# capstone.net
KiCad netlist of a schematic drawn in EAGLE
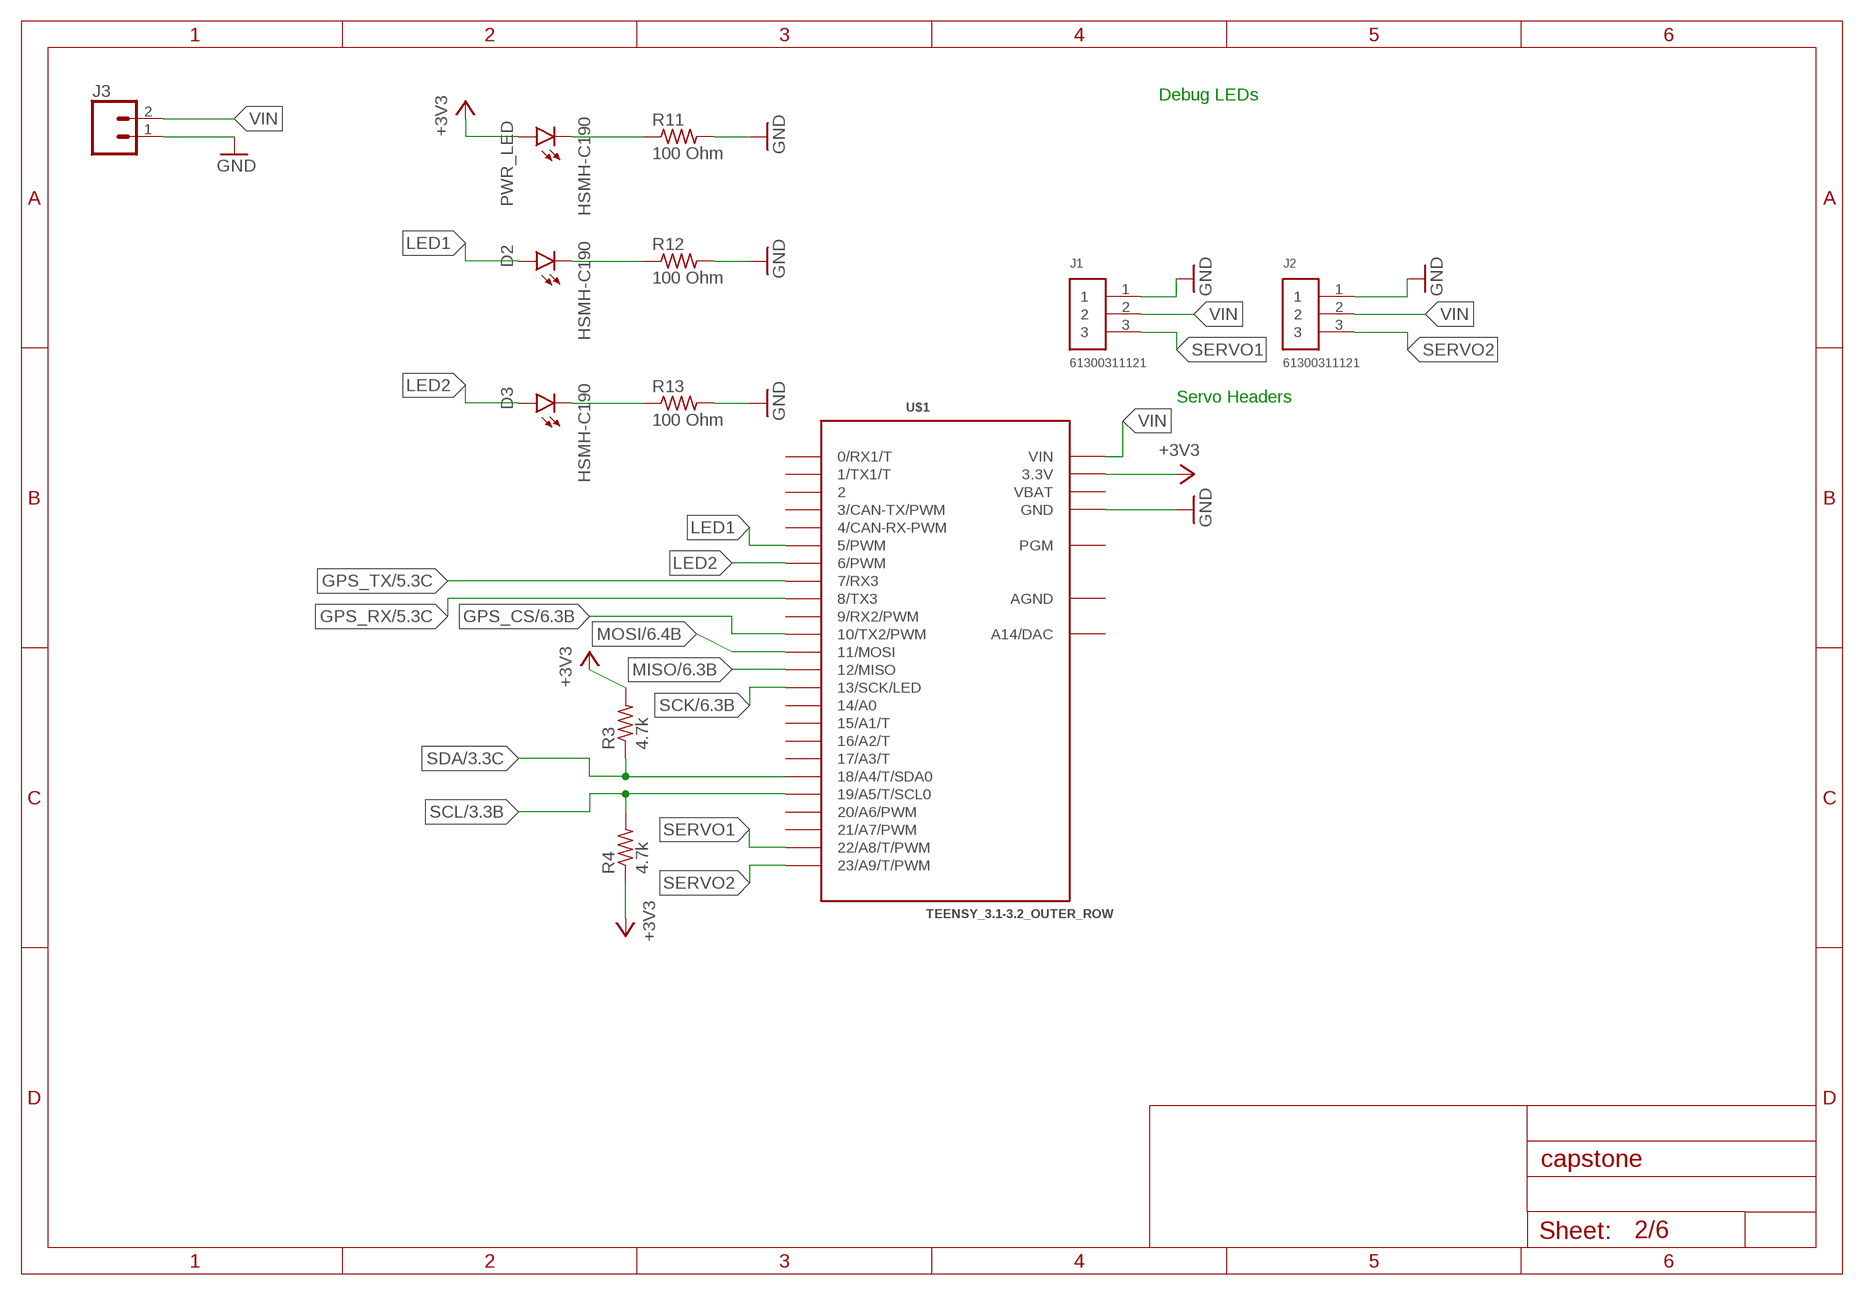
[diagram p0: schematic, sheet 2]
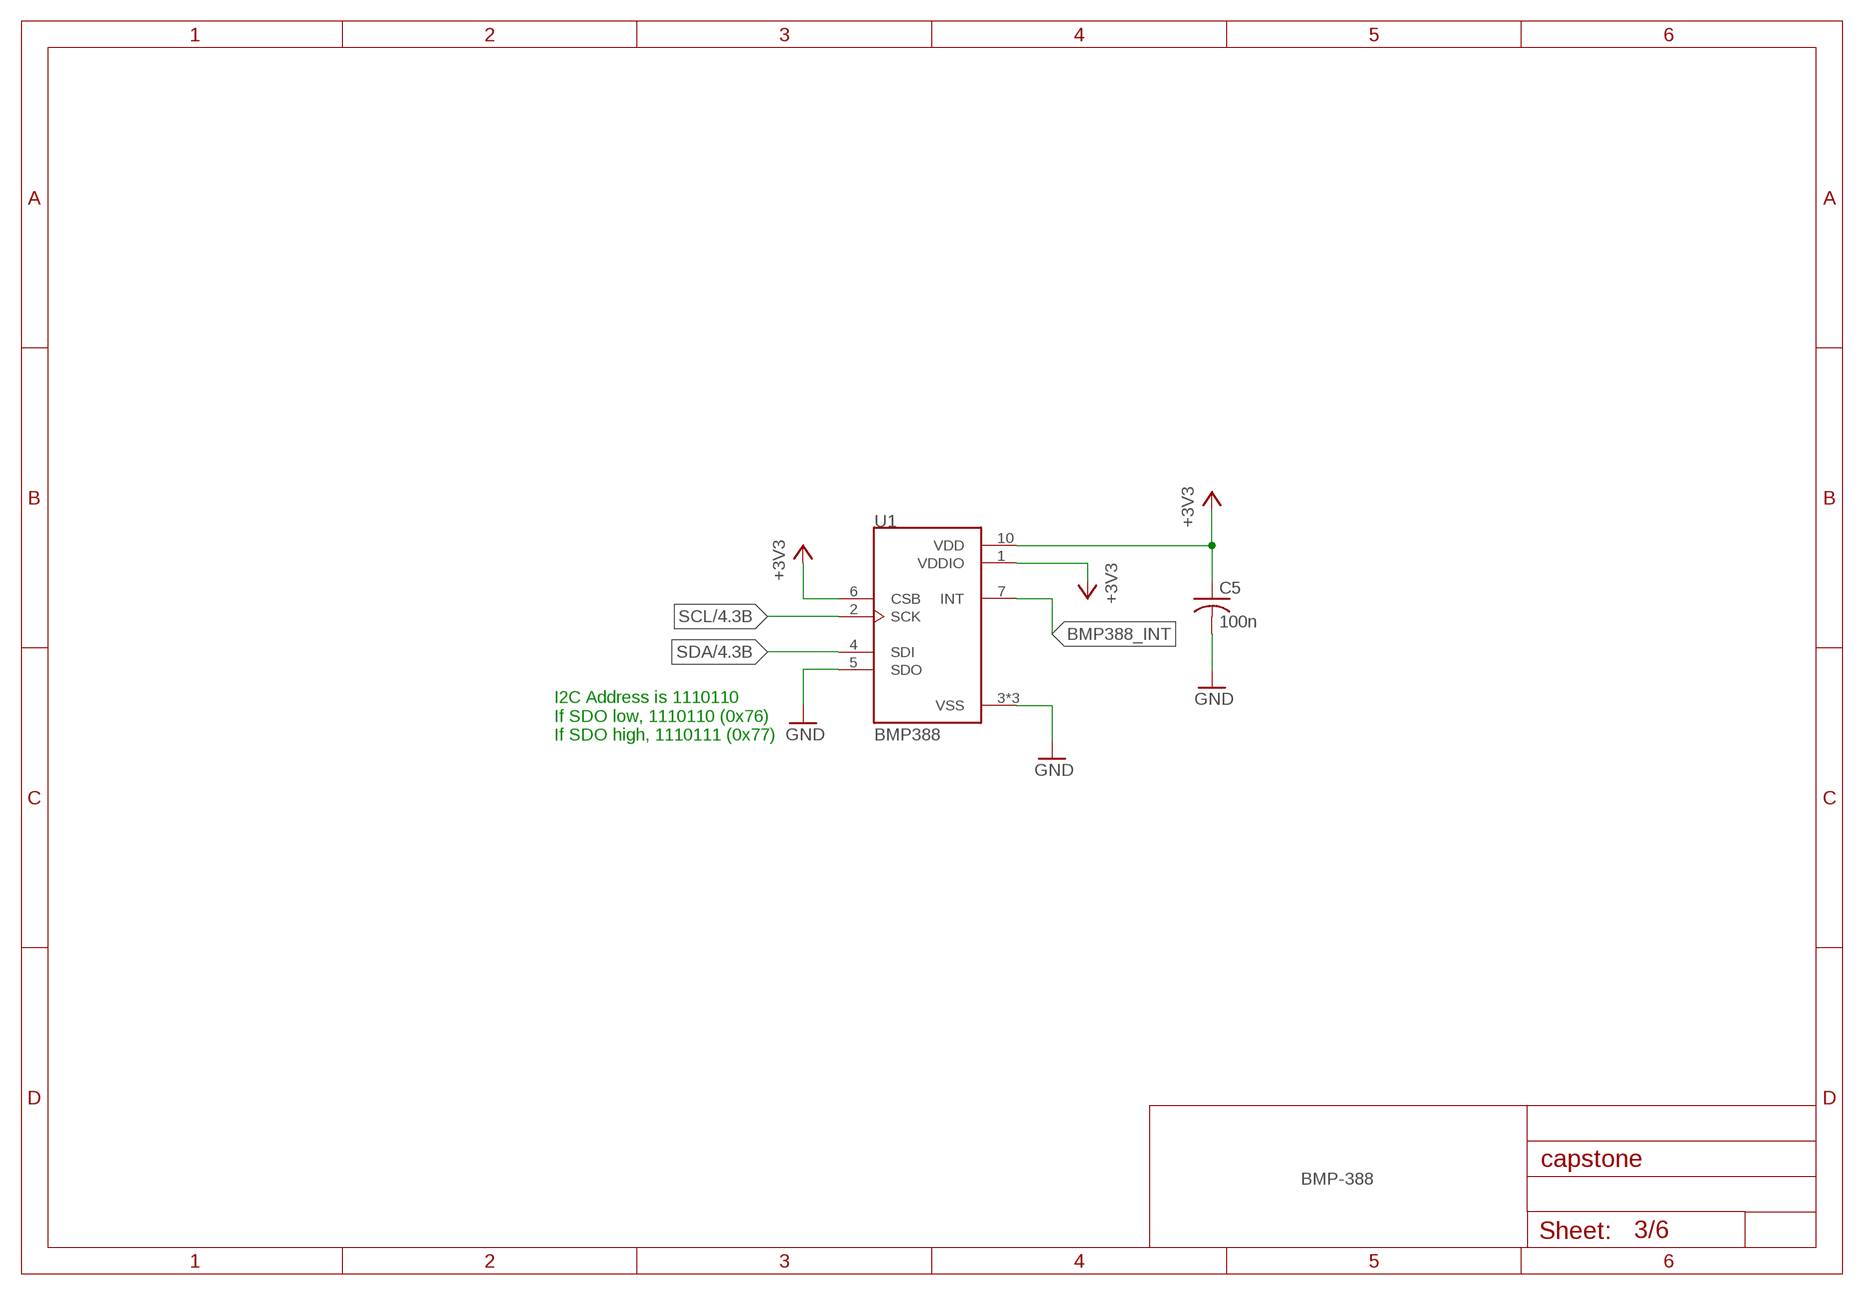
[diagram p1: schematic, sheet 3]
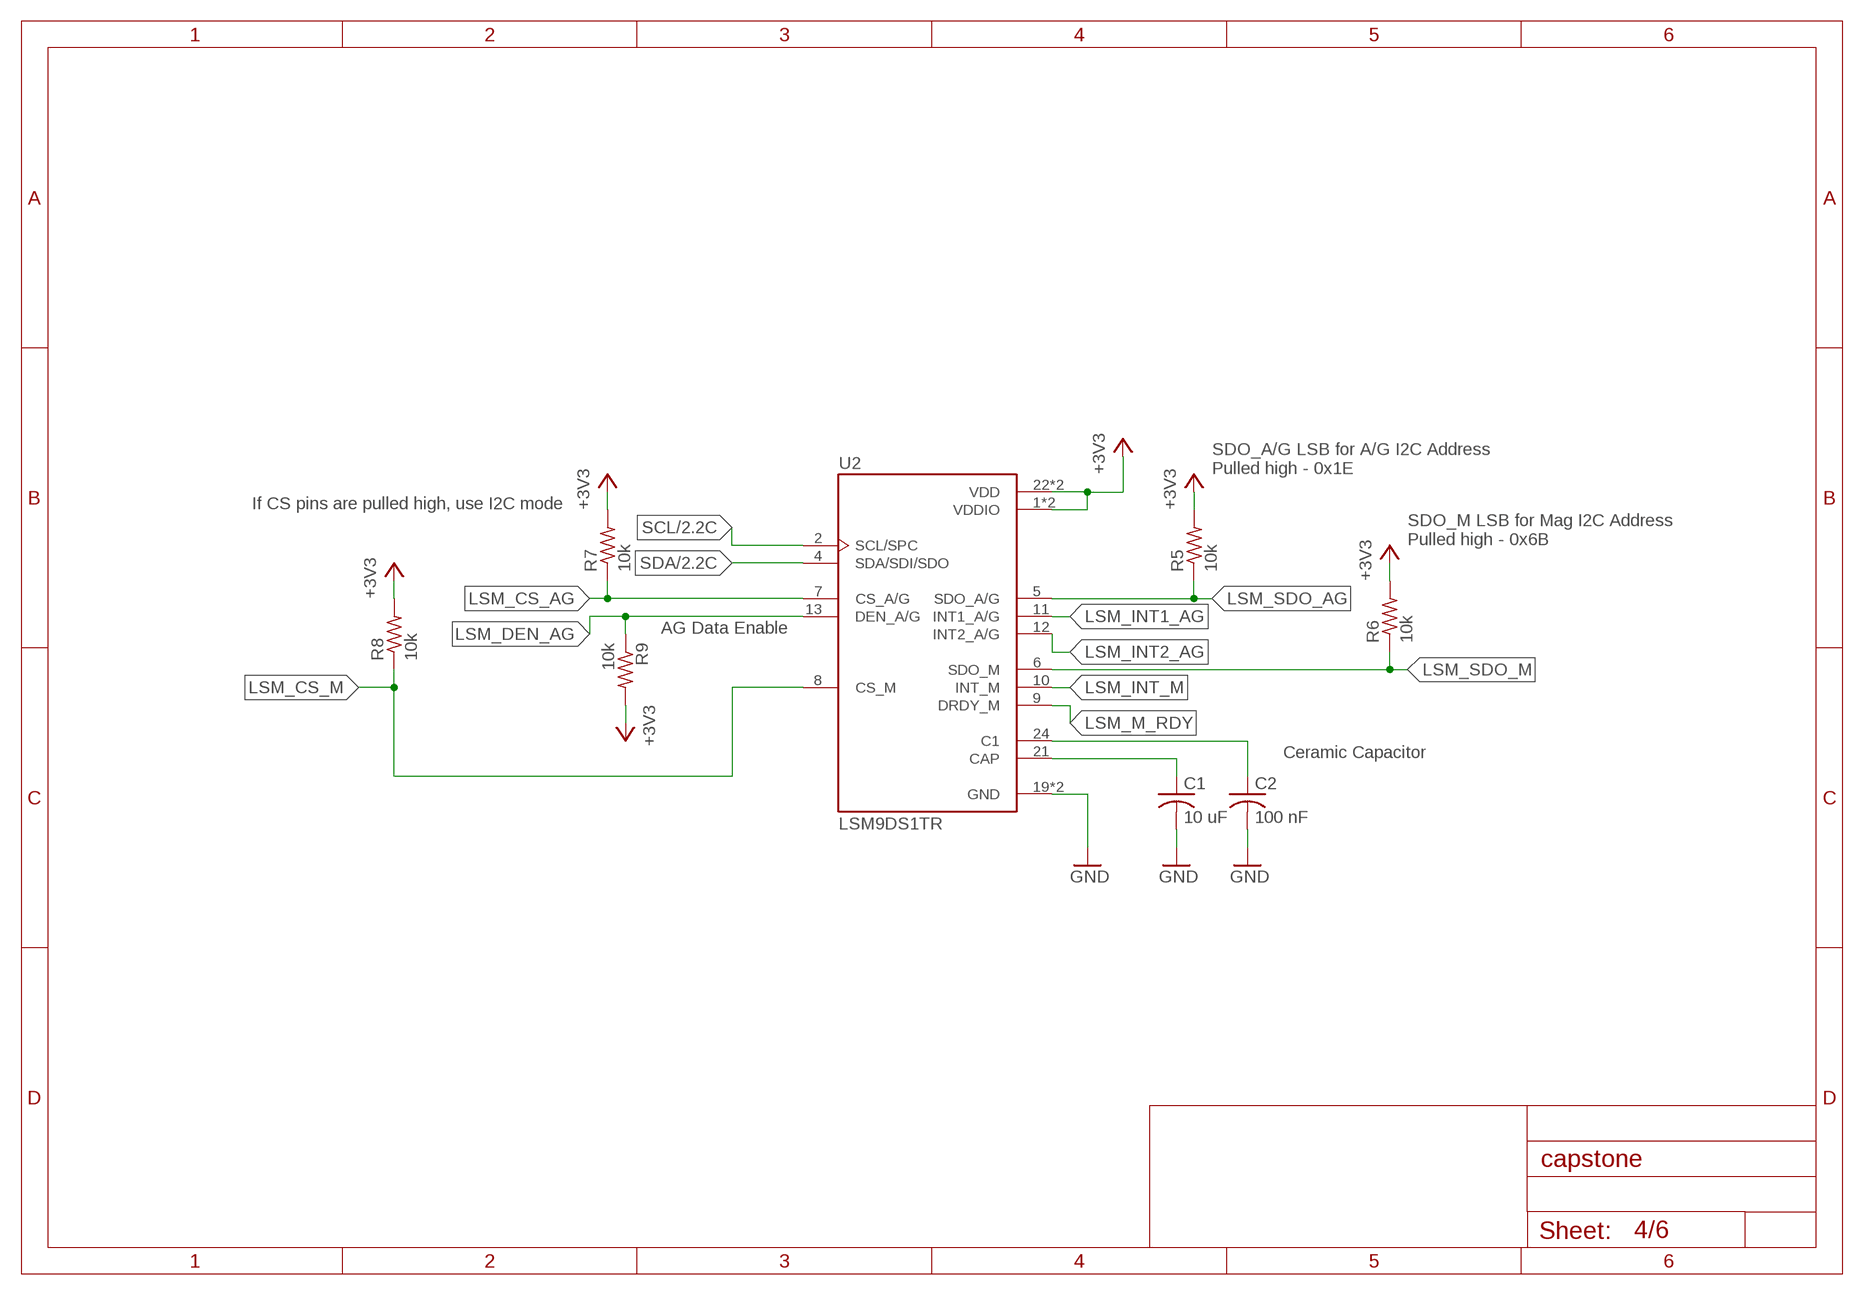
[diagram p2: schematic, sheet 4]
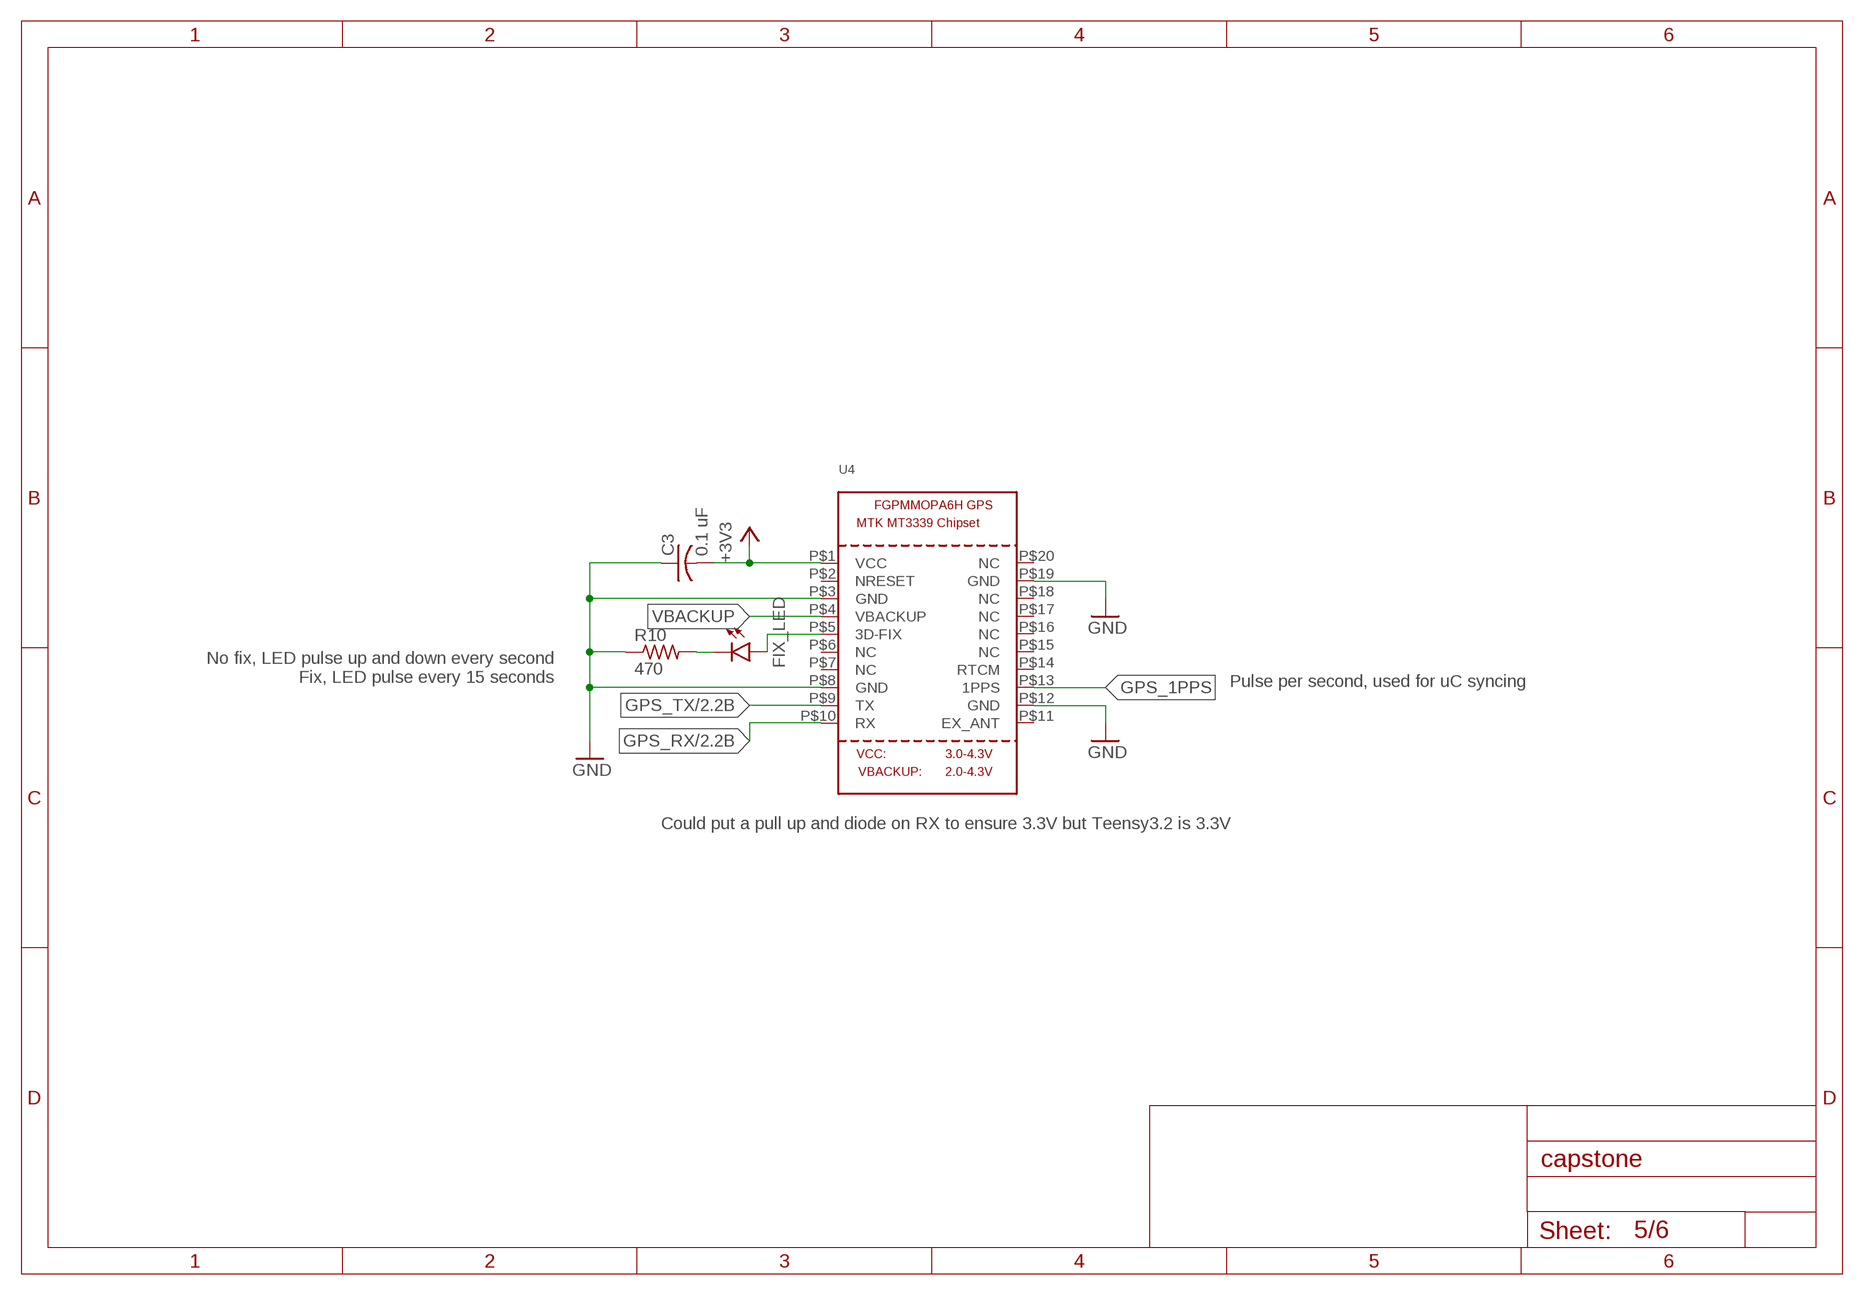
[diagram p3: schematic, sheet 5]
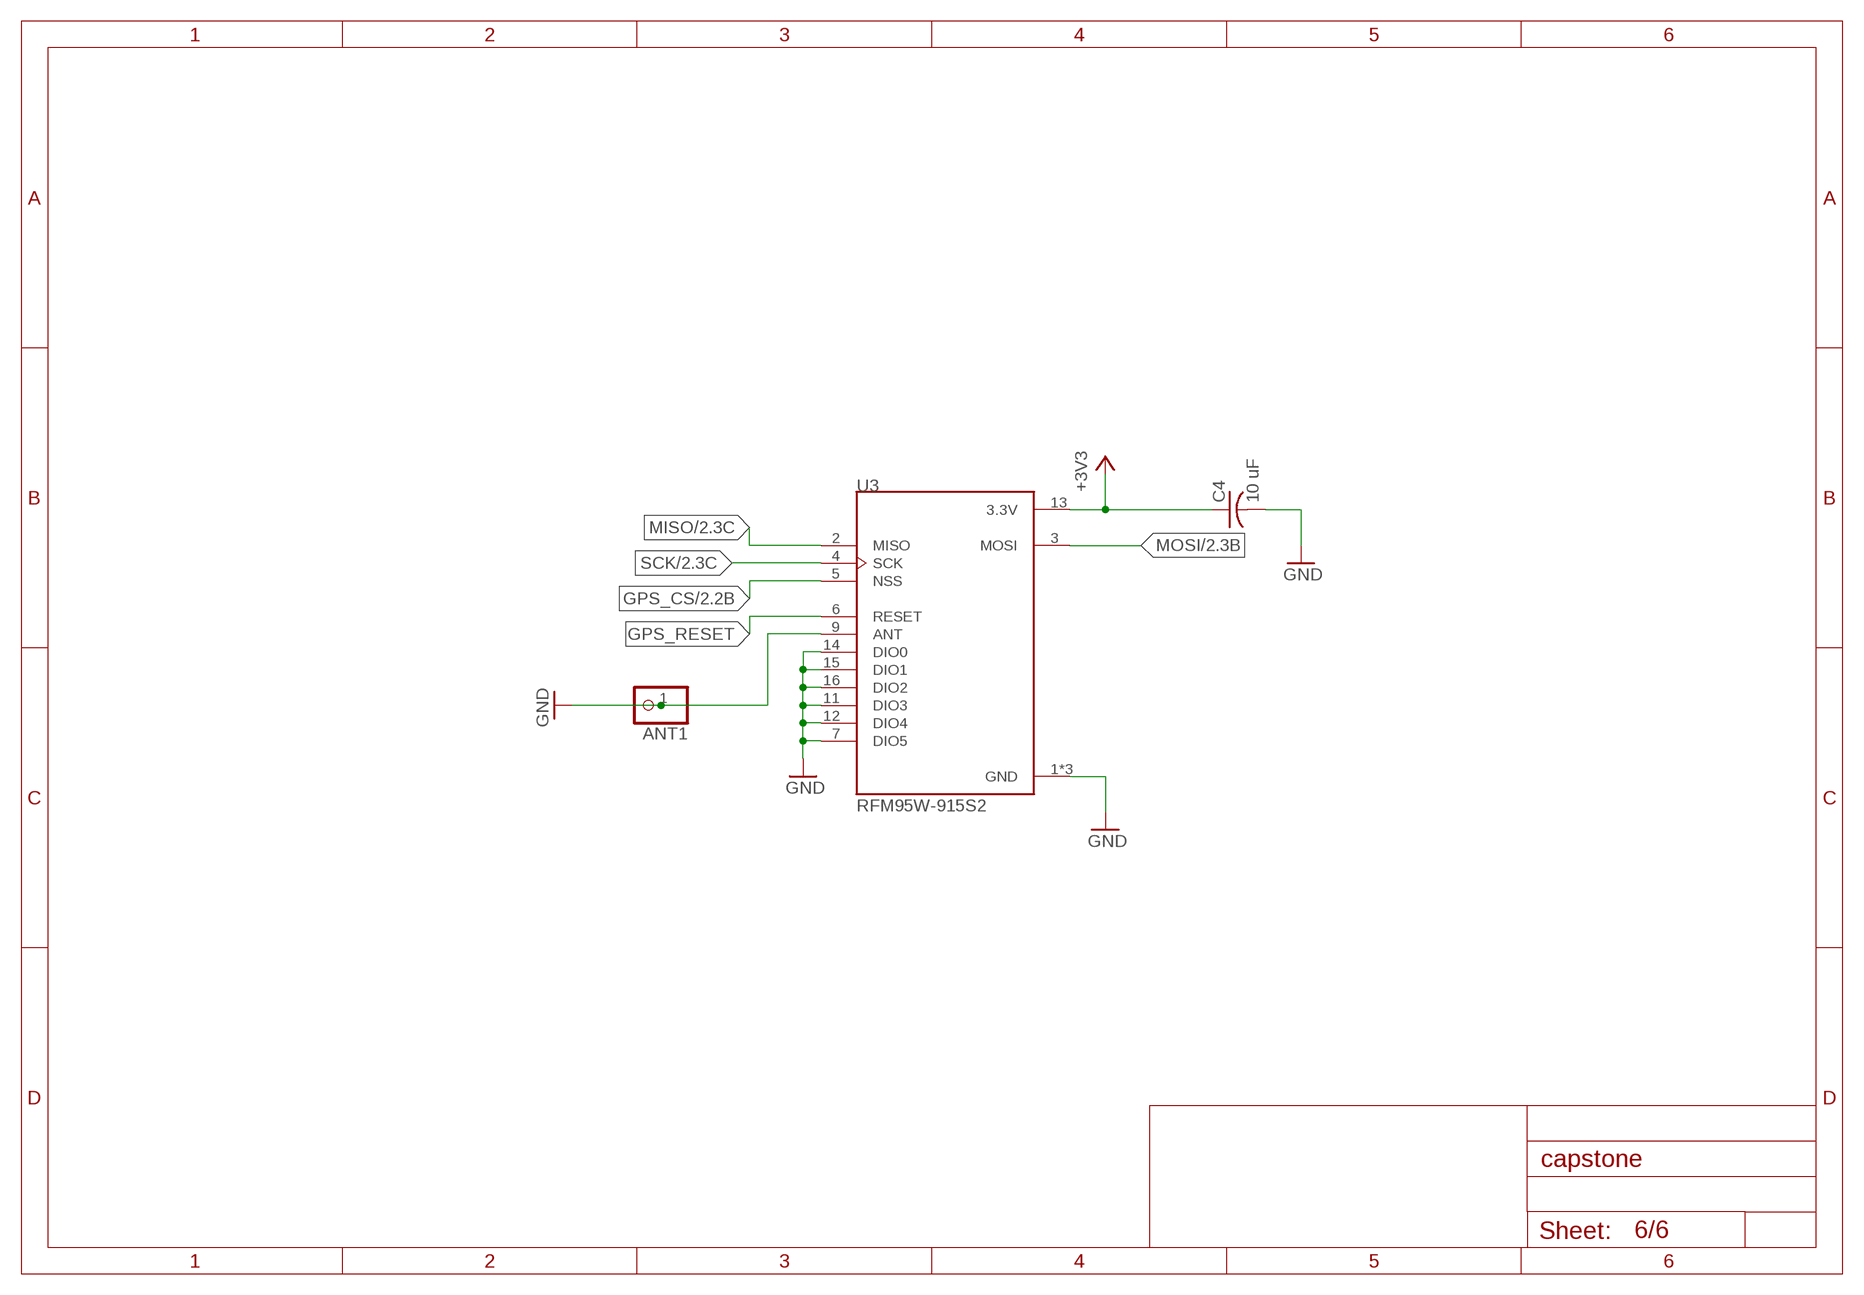
[diagram p4: schematic, sheet 6]

(export (version "E")
  (design (tool "Eeschema 10.0.6"))
  (components
    (comp (ref "D2")
      (value "HSMH-C190")
      (footprint "eagle-import:LED-0603")
      (fields
        (field (name "DIGIKEY_PART_NUMBER") "516-1420-1-ND")
        (field (name "MANUFACTURER") "Broadcom Limited")
        (field (name "CREATED_BY") "PCBLayout.com")
      )
      (libsource (lib "eagle-import") (part "HSMH-C190"))
    )
    (comp (ref "D3")
      (value "HSMH-C190")
      (footprint "eagle-import:LED-0603")
      (fields
        (field (name "DIGIKEY_PART_NUMBER") "516-1420-1-ND")
        (field (name "MANUFACTURER") "Broadcom Limited")
        (field (name "CREATED_BY") "PCBLayout.com")
      )
      (libsource (lib "eagle-import") (part "HSMH-C190"))
    )
    (comp (ref "J1")
      (value "61300311121")
      (footprint "eagle-import:61300311121")
      (fields
        (field (name "DIGI_KEY_PART_NUMBER") "732-5316-ND")
        (field (name "MANUFACTURER") "Wurth Electronics Inc.")
        (field (name "CREATED_BY") "PCBLayout.com")
      )
      (libsource (lib "eagle-import") (part "61300311121"))
    )
    (comp (ref "J2")
      (value "61300311121")
      (footprint "eagle-import:61300311121")
      (fields
        (field (name "DIGI_KEY_PART_NUMBER") "732-5316-ND")
        (field (name "MANUFACTURER") "Wurth Electronics Inc.")
        (field (name "CREATED_BY") "PCBLayout.com")
      )
      (libsource (lib "eagle-import") (part "61300311121"))
    )
    (comp (ref "J3")
      (value "CONN_02")
      (footprint "eagle-import:1X02")
      (libsource (lib "eagle-import") (part "CONN_02"))
    )
    (comp (ref "PWR_LED")
      (value "HSMH-C190")
      (footprint "eagle-import:LED-0603")
      (fields
        (field (name "DIGIKEY_PART_NUMBER") "516-1420-1-ND")
        (field (name "MANUFACTURER") "Broadcom Limited")
        (field (name "CREATED_BY") "PCBLayout.com")
      )
      (libsource (lib "eagle-import") (part "HSMH-C190"))
    )
    (comp (ref "R3")
      (value "4.7k")
      (footprint "eagle-import:R0603")
      (libsource (lib "eagle-import") (part "R-US_R0603"))
    )
    (comp (ref "R4")
      (value "4.7k")
      (footprint "eagle-import:R0603")
      (libsource (lib "eagle-import") (part "R-US_R0603"))
    )
    (comp (ref "R11")
      (value "100 Ohm")
      (footprint "eagle-import:R0603")
      (libsource (lib "eagle-import") (part "R-US_R0603"))
    )
    (comp (ref "R12")
      (value "100 Ohm")
      (footprint "eagle-import:R0603")
      (libsource (lib "eagle-import") (part "R-US_R0603"))
    )
    (comp (ref "R13")
      (value "100 Ohm")
      (footprint "eagle-import:R0603")
      (libsource (lib "eagle-import") (part "R-US_R0603"))
    )
    (comp (ref "U$1")
      (value "TEENSY_3.1-3.2_OUTER_ROW")
      (footprint "eagle-import:TEENSY_3.0-3.2&LC_OUTER_ROW")
      (libsource (lib "eagle-import") (part "TEENSY_3.1-3.2_OUTER_ROW"))
    )
    (comp (ref "C3")
      (value "0.1 uF")
      (footprint "eagle-import:C0603")
      (libsource (lib "eagle-import") (part "resistor_348_C-USC0603"))
    )
    (comp (ref "FIX_LED")
      (value "HSMH-C190")
      (footprint "eagle-import:LED-0603")
      (fields
        (field (name "DIGIKEY_PART_NUMBER") "516-1420-1-ND")
        (field (name "MANUFACTURER") "Broadcom Limited")
        (field (name "CREATED_BY") "PCBLayout.com")
      )
      (libsource (lib "eagle-import") (part "HSMH-C190"))
    )
    (comp (ref "R10")
      (value "470")
      (footprint "eagle-import:R0603")
      (libsource (lib "eagle-import") (part "R-US_R0603"))
    )
    (comp (ref "U4")
      (value "GPS_FGPMMOPA6H")
      (footprint "eagle-import:FGPMMOPA6H")
      (libsource (lib "eagle-import") (part "GPS_FGPMMOPA6H"))
    )
    (comp (ref "C1")
      (value "10 uF")
      (footprint "eagle-import:C0603")
      (libsource (lib "eagle-import") (part "resistor_348_C-USC0603"))
    )
    (comp (ref "C2")
      (value "100 nF")
      (footprint "eagle-import:C0603")
      (libsource (lib "eagle-import") (part "resistor_348_C-USC0603"))
    )
    (comp (ref "R5")
      (value "10k")
      (footprint "eagle-import:R0603")
      (libsource (lib "eagle-import") (part "R-US_R0603"))
    )
    (comp (ref "R6")
      (value "10k")
      (footprint "eagle-import:R0603")
      (libsource (lib "eagle-import") (part "R-US_R0603"))
    )
    (comp (ref "R7")
      (value "10k")
      (footprint "eagle-import:R0603")
      (libsource (lib "eagle-import") (part "R-US_R0603"))
    )
    (comp (ref "R8")
      (value "10k")
      (footprint "eagle-import:R0603")
      (libsource (lib "eagle-import") (part "R-US_R0603"))
    )
    (comp (ref "R9")
      (value "10k")
      (footprint "eagle-import:R0603")
      (libsource (lib "eagle-import") (part "R-US_R0603"))
    )
    (comp (ref "U2")
      (value "LSM9DS1TR")
      (footprint "eagle-import:PQFN43P300X350X102-24N")
      (fields (field (name "DIGI-KEY_PART_NUMBER") "497-14946-1-ND") (field (name "MF") "STMicroelectronics"))
      (libsource (lib "eagle-import") (part "LSM9DS1TR"))
    )
    (comp (ref "C5")
      (value "100n")
      (footprint "eagle-import:C0603")
      (libsource (lib "eagle-import") (part "C-USC0603"))
    )
    (comp (ref "U1")
      (value "BMP388")
      (footprint "eagle-import:PQFN50P200X200X80-10N")
      (fields (field (name "DIGI-KEY_PART_NUMBER") "828-1079-1-ND") (field (name "MF") "Bosch Sensortec"))
      (libsource (lib "eagle-import") (part "BMP388"))
    )
    (comp (ref "ANT1")
      (value "PINHD-1X1")
      (footprint "eagle-import:1X01")
      (libsource (lib "eagle-import") (part "PINHD-1X1"))
    )
    (comp (ref "C4")
      (value "10 uF")
      (footprint "eagle-import:C0603")
      (libsource (lib "eagle-import") (part "resistor_348_C-USC0603"))
    )
    (comp (ref "U3")
      (value "RFM95W-915S2")
      (footprint "eagle-import:XCVR_RFM95W-915S2")
      (fields (field (name "DIGI-KEY_PART_NUMBER") "RFM95W-915S2-ND") (field (name "MF") "RF Solutions"))
      (libsource (lib "eagle-import") (part "RFM95W-915S2"))
    )
  )
  (nets
    (net (code "1") (name "+3V3") (class "Default")
      (node (ref "C3") (pin "2") (pinfunction "2_2") (pintype "passive"))
      (node (ref "C4") (pin "1") (pinfunction "1_1") (pintype "passive"))
      (node (ref "C5") (pin "1") (pinfunction "1_1") (pintype "passive"))
      (node (ref "PWR_LED") (pin "A") (pinfunction "A_A") (pintype "passive"))
      (node (ref "R3") (pin "2") (pinfunction "2_2") (pintype "passive"))
      (node (ref "R4") (pin "1") (pinfunction "1_1") (pintype "passive"))
      (node (ref "R5") (pin "2") (pinfunction "2_2") (pintype "passive"))
      (node (ref "R6") (pin "2") (pinfunction "2_2") (pintype "passive"))
      (node (ref "R7") (pin "2") (pinfunction "2_2") (pintype "passive"))
      (node (ref "R8") (pin "2") (pinfunction "2_2") (pintype "passive"))
      (node (ref "R9") (pin "2") (pinfunction "2_2") (pintype "passive"))
      (node (ref "U$1") (pin "3.3V") (pinfunction "3.3V_3.3V") (pintype "power_in"))
      (node (ref "U$1") (pin "3.3V1") (pinfunction "3.3V_3.3V1") (pintype "power_in"))
      (node (ref "U1") (pin "1") (pinfunction "VDDIO_1") (pintype "power_in"))
      (node (ref "U1") (pin "10") (pinfunction "VDD_10") (pintype "power_in"))
      (node (ref "U1") (pin "6") (pinfunction "CSB_6") (pintype "input"))
      (node (ref "U2") (pin "1") (pinfunction "VDDIO_1") (pintype "power_in"))
      (node (ref "U2") (pin "22") (pinfunction "VDD_22") (pintype "power_in"))
      (node (ref "U2") (pin "23") (pinfunction "VDD_23") (pintype "power_in"))
      (node (ref "U2") (pin "3") (pinfunction "VDDIO_3") (pintype "power_in"))
      (node (ref "U3") (pin "13") (pinfunction "3.3V_13") (pintype "power_in"))
      (node (ref "U4") (pin "P$1") (pinfunction "VCC_P$1") (pintype "bidirectional"))
    )
    (net (code "2") (name "AGND") (class "Default")
      (node (ref "U$1") (pin "AGND") (pinfunction "AGND_AGND") (pintype "power_in"))
    )
    (net (code "3") (name "BMP388_INT") (class "Default")
      (node (ref "U1") (pin "7") (pinfunction "INT_7") (pintype "output"))
    )
    (net (code "4") (name "GND") (class "Default")
      (node (ref "ANT1") (pin "1") (pinfunction "1_1") (pintype "passive"))
      (node (ref "C1") (pin "2") (pinfunction "2_2") (pintype "passive"))
      (node (ref "C2") (pin "2") (pinfunction "2_2") (pintype "passive"))
      (node (ref "C3") (pin "1") (pinfunction "1_1") (pintype "passive"))
      (node (ref "C4") (pin "2") (pinfunction "2_2") (pintype "passive"))
      (node (ref "C5") (pin "2") (pinfunction "2_2") (pintype "passive"))
      (node (ref "J1") (pin "1") (pinfunction "1_1") (pintype "passive"))
      (node (ref "J2") (pin "1") (pinfunction "1_1") (pintype "passive"))
      (node (ref "J3") (pin "1") (pinfunction "1_1") (pintype "passive"))
      (node (ref "R10") (pin "1") (pinfunction "1_1") (pintype "passive"))
      (node (ref "R11") (pin "2") (pinfunction "2_2") (pintype "passive"))
      (node (ref "R12") (pin "2") (pinfunction "2_2") (pintype "passive"))
      (node (ref "R13") (pin "2") (pinfunction "2_2") (pintype "passive"))
      (node (ref "U$1") (pin "GND") (pinfunction "GND_GND") (pintype "power_in"))
      (node (ref "U$1") (pin "GND1") (pinfunction "GND_GND1") (pintype "power_in"))
      (node (ref "U1") (pin "3") (pinfunction "VSS_3") (pintype "power_in"))
      (node (ref "U1") (pin "5") (pinfunction "SDO_5") (pintype "bidirectional"))
      (node (ref "U1") (pin "8") (pinfunction "VSS_8") (pintype "power_in"))
      (node (ref "U1") (pin "9") (pinfunction "VSS_9") (pintype "power_in"))
      (node (ref "U2") (pin "19") (pinfunction "GND_19") (pintype "power_in"))
      (node (ref "U2") (pin "20") (pinfunction "GND_20") (pintype "power_in"))
      (node (ref "U3") (pin "1") (pinfunction "GND_1") (pintype "power_in"))
      (node (ref "U3") (pin "10") (pinfunction "GND_10") (pintype "power_in"))
      (node (ref "U3") (pin "11") (pinfunction "DIO3_11") (pintype "bidirectional"))
      (node (ref "U3") (pin "12") (pinfunction "DIO4_12") (pintype "bidirectional"))
      (node (ref "U3") (pin "14") (pinfunction "DIO0_14") (pintype "bidirectional"))
      (node (ref "U3") (pin "15") (pinfunction "DIO1_15") (pintype "bidirectional"))
      (node (ref "U3") (pin "16") (pinfunction "DIO2_16") (pintype "bidirectional"))
      (node (ref "U3") (pin "7") (pinfunction "DIO5_7") (pintype "bidirectional"))
      (node (ref "U3") (pin "8") (pinfunction "GND_8") (pintype "power_in"))
      (node (ref "U3") (pin "9") (pinfunction "ANT_9") (pintype "bidirectional"))
      (node (ref "U4") (pin "P$12") (pinfunction "GND_P$12") (pintype "bidirectional"))
      (node (ref "U4") (pin "P$19") (pinfunction "GND_P$19") (pintype "bidirectional"))
      (node (ref "U4") (pin "P$3") (pinfunction "GND_P$3") (pintype "bidirectional"))
      (node (ref "U4") (pin "P$8") (pinfunction "GND_P$8") (pintype "bidirectional"))
    )
    (net (code "5") (name "GPS_1PPS") (class "Default")
      (node (ref "U4") (pin "P$13") (pinfunction "1PPS_P$13") (pintype "bidirectional"))
    )
    (net (code "6") (name "GPS_CS") (class "Default")
      (node (ref "U$1") (pin "10") (pinfunction "10/TX2/PWM_10") (pintype "bidirectional"))
      (node (ref "U3") (pin "5") (pinfunction "NSS_5") (pintype "input"))
    )
    (net (code "7") (name "GPS_RESET") (class "Default")
      (node (ref "U3") (pin "6") (pinfunction "RESET_6") (pintype "bidirectional"))
    )
    (net (code "8") (name "GPS_RX") (class "Default")
      (node (ref "U$1") (pin "8") (pinfunction "8/TX3_8") (pintype "bidirectional"))
      (node (ref "U4") (pin "P$10") (pinfunction "RX_P$10") (pintype "bidirectional"))
    )
    (net (code "9") (name "GPS_TX") (class "Default")
      (node (ref "U$1") (pin "7") (pinfunction "7/RX3_7") (pintype "bidirectional"))
      (node (ref "U4") (pin "P$9") (pinfunction "TX_P$9") (pintype "bidirectional"))
    )
    (net (code "10") (name "LED1") (class "Default")
      (node (ref "D2") (pin "A") (pinfunction "A_A") (pintype "passive"))
      (node (ref "U$1") (pin "5") (pinfunction "5/PWM_5") (pintype "bidirectional"))
    )
    (net (code "11") (name "LED2") (class "Default")
      (node (ref "D3") (pin "A") (pinfunction "A_A") (pintype "passive"))
      (node (ref "U$1") (pin "6") (pinfunction "6/PWM_6") (pintype "bidirectional"))
    )
    (net (code "12") (name "LSM_CS_AG") (class "Default")
      (node (ref "R7") (pin "1") (pinfunction "1_1") (pintype "passive"))
      (node (ref "U2") (pin "7") (pinfunction "CS_A/G_7") (pintype "input"))
    )
    (net (code "13") (name "LSM_CS_M") (class "Default")
      (node (ref "R8") (pin "1") (pinfunction "1_1") (pintype "passive"))
      (node (ref "U2") (pin "8") (pinfunction "CS_M_8") (pintype "input"))
    )
    (net (code "14") (name "LSM_DEN_AG") (class "Default")
      (node (ref "R9") (pin "1") (pinfunction "1_1") (pintype "passive"))
      (node (ref "U2") (pin "13") (pinfunction "DEN_A/G_13") (pintype "input"))
    )
    (net (code "15") (name "LSM_INT1_AG") (class "Default")
      (node (ref "U2") (pin "11") (pinfunction "INT1_A/G_11") (pintype "output"))
    )
    (net (code "16") (name "LSM_INT2_AG") (class "Default")
      (node (ref "U2") (pin "12") (pinfunction "INT2_A/G_12") (pintype "output"))
    )
    (net (code "17") (name "LSM_INT_M") (class "Default")
      (node (ref "U2") (pin "10") (pinfunction "INT_M_10") (pintype "output"))
    )
    (net (code "18") (name "LSM_M_RDY") (class "Default")
      (node (ref "U2") (pin "9") (pinfunction "DRDY_M_9") (pintype "output"))
    )
    (net (code "19") (name "LSM_SDO_AG") (class "Default")
      (node (ref "R5") (pin "1") (pinfunction "1_1") (pintype "passive"))
      (node (ref "U2") (pin "5") (pinfunction "SDO_A/G_5") (pintype "output"))
    )
    (net (code "20") (name "LSM_SDO_M") (class "Default")
      (node (ref "R6") (pin "1") (pinfunction "1_1") (pintype "passive"))
      (node (ref "U2") (pin "6") (pinfunction "SDO_M_6") (pintype "output"))
    )
    (net (code "21") (name "MISO") (class "Default")
      (node (ref "U$1") (pin "12") (pinfunction "12/MISO_12") (pintype "bidirectional"))
      (node (ref "U3") (pin "2") (pinfunction "MISO_2") (pintype "input"))
    )
    (net (code "22") (name "MOSI") (class "Default")
      (node (ref "U$1") (pin "11") (pinfunction "11/MOSI_11") (pintype "bidirectional"))
      (node (ref "U3") (pin "3") (pinfunction "MOSI_3") (pintype "output"))
    )
    (net (code "23") (name "Net-(D2-PadC)") (class "Default")
      (node (ref "D2") (pin "C") (pinfunction "C_C") (pintype "passive"))
      (node (ref "R12") (pin "1") (pinfunction "1_1") (pintype "passive"))
    )
    (net (code "24") (name "Net-(D3-PadC)") (class "Default")
      (node (ref "D3") (pin "C") (pinfunction "C_C") (pintype "passive"))
      (node (ref "R13") (pin "1") (pinfunction "1_1") (pintype "passive"))
    )
    (net (code "25") (name "Net-(FIX_LED-PadC)") (class "Default")
      (node (ref "FIX_LED") (pin "C") (pinfunction "C_C") (pintype "passive"))
      (node (ref "R10") (pin "2") (pinfunction "2_2") (pintype "passive"))
    )
    (net (code "26") (name "Net-(PWR_LED-PadC)") (class "Default")
      (node (ref "PWR_LED") (pin "C") (pinfunction "C_C") (pintype "passive"))
      (node (ref "R11") (pin "1") (pinfunction "1_1") (pintype "passive"))
    )
    (net (code "27") (name "Net-(U2-C1)") (class "Default")
      (node (ref "C2") (pin "1") (pinfunction "1_1") (pintype "passive"))
      (node (ref "U2") (pin "24") (pinfunction "C1_24") (pintype "passive"))
    )
    (net (code "28") (name "Net-(U2-CAP)") (class "Default")
      (node (ref "C1") (pin "1") (pinfunction "1_1") (pintype "passive"))
      (node (ref "U2") (pin "21") (pinfunction "CAP_21") (pintype "passive"))
    )
    (net (code "29") (name "Net-(U4-3D-FIX)") (class "Default")
      (node (ref "FIX_LED") (pin "A") (pinfunction "A_A") (pintype "passive"))
      (node (ref "U4") (pin "P$5") (pinfunction "3D-FIX_P$5") (pintype "bidirectional"))
    )
    (net (code "30") (name "SCK") (class "Default")
      (node (ref "U$1") (pin "13") (pinfunction "13/SCK/LED_13") (pintype "bidirectional"))
      (node (ref "U3") (pin "4") (pinfunction "SCK_4") (pintype "input"))
    )
    (net (code "31") (name "SCL") (class "Default")
      (node (ref "R4") (pin "2") (pinfunction "2_2") (pintype "passive"))
      (node (ref "U$1") (pin "19/A5") (pinfunction "19/A5/T/SCL0_19/A5") (pintype "bidirectional"))
      (node (ref "U1") (pin "2") (pinfunction "SCK_2") (pintype "input"))
      (node (ref "U2") (pin "2") (pinfunction "SCL/SPC_2") (pintype "input"))
    )
    (net (code "32") (name "SDA") (class "Default")
      (node (ref "R3") (pin "1") (pinfunction "1_1") (pintype "passive"))
      (node (ref "U$1") (pin "18/A4") (pinfunction "18/A4/T/SDA0_18/A4") (pintype "bidirectional"))
      (node (ref "U1") (pin "4") (pinfunction "SDI_4") (pintype "bidirectional"))
      (node (ref "U2") (pin "4") (pinfunction "SDA/SDI/SDO_4") (pintype "bidirectional"))
    )
    (net (code "33") (name "SERVO1") (class "Default")
      (node (ref "J1") (pin "3") (pinfunction "3_3") (pintype "passive"))
      (node (ref "U$1") (pin "22/A8") (pinfunction "22/A8/T/PWM_22/A8") (pintype "bidirectional"))
    )
    (net (code "34") (name "SERVO2") (class "Default")
      (node (ref "J2") (pin "3") (pinfunction "3_3") (pintype "passive"))
      (node (ref "U$1") (pin "23/A9") (pinfunction "23/A9/T/PWM_23/A9") (pintype "bidirectional"))
    )
    (net (code "35") (name "VBACKUP") (class "Default")
      (node (ref "U4") (pin "P$4") (pinfunction "VBACKUP_P$4") (pintype "bidirectional"))
    )
    (net (code "36") (name "VBAT") (class "Default")
      (node (ref "U$1") (pin "VBAT") (pinfunction "VBAT_VBAT") (pintype "power_in"))
    )
    (net (code "37") (name "VIN") (class "Default")
      (node (ref "J1") (pin "2") (pinfunction "2_2") (pintype "passive"))
      (node (ref "J2") (pin "2") (pinfunction "2_2") (pintype "passive"))
      (node (ref "J3") (pin "2") (pinfunction "2_2") (pintype "passive"))
      (node (ref "U$1") (pin "VIN") (pinfunction "VIN_VIN") (pintype "power_in"))
    )
    (net (code "38") (name "unconnected-(U$1-0{slash}RX1{slash}T-Pad0)") (class "Default")
      (node (ref "U$1") (pin "0") (pinfunction "0/RX1/T_0") (pintype "bidirectional"))
    )
    (net (code "39") (name "unconnected-(U$1-1{slash}TX1{slash}T-Pad1)") (class "Default")
      (node (ref "U$1") (pin "1") (pinfunction "1/TX1/T_1") (pintype "bidirectional"))
    )
    (net (code "40") (name "unconnected-(U$1-3{slash}CAN-TX{slash}PWM-Pad3)") (class "Default")
      (node (ref "U$1") (pin "3") (pinfunction "3/CAN-TX/PWM_3") (pintype "bidirectional"))
    )
    (net (code "41") (name "unconnected-(U$1-4{slash}CAN-RX-PWM-Pad4)") (class "Default")
      (node (ref "U$1") (pin "4") (pinfunction "4/CAN-RX-PWM_4") (pintype "bidirectional"))
    )
    (net (code "42") (name "unconnected-(U$1-9{slash}RX2{slash}PWM-Pad9)") (class "Default")
      (node (ref "U$1") (pin "9") (pinfunction "9/RX2/PWM_9") (pintype "bidirectional"))
    )
    (net (code "43") (name "unconnected-(U$1-15{slash}A1{slash}T-Pad15{slash}A1)") (class "Default")
      (node (ref "U$1") (pin "15/A1") (pinfunction "15/A1/T_15/A1") (pintype "bidirectional"))
    )
    (net (code "44") (name "unconnected-(U$1-16{slash}A2{slash}T-Pad16{slash}A2)") (class "Default")
      (node (ref "U$1") (pin "16/A2") (pinfunction "16/A2/T_16/A2") (pintype "bidirectional"))
    )
    (net (code "45") (name "unconnected-(U$1-17{slash}A3{slash}T-Pad17{slash}A3)") (class "Default")
      (node (ref "U$1") (pin "17/A3") (pinfunction "17/A3/T_17/A3") (pintype "bidirectional"))
    )
    (net (code "46") (name "unconnected-(U$1-20{slash}A6{slash}PWM-Pad20{slash}A6)") (class "Default")
      (node (ref "U$1") (pin "20/A6") (pinfunction "20/A6/PWM_20/A6") (pintype "bidirectional"))
    )
    (net (code "47") (name "unconnected-(U$1-21{slash}A7{slash}PWM-Pad21{slash}A7)") (class "Default")
      (node (ref "U$1") (pin "21/A7") (pinfunction "21/A7/PWM_21/A7") (pintype "bidirectional"))
    )
    (net (code "48") (name "unconnected-(U$1-A14{slash}DAC-PadRESET{slash}DAC)") (class "Default")
      (node (ref "U$1") (pin "RESET/DAC") (pinfunction "A14/DAC_RESET/DAC") (pintype "bidirectional"))
    )
    (net (code "49") (name "unconnected-(U$1-Pad2)") (class "Default")
      (node (ref "U$1") (pin "2") (pinfunction "2_2") (pintype "bidirectional"))
    )
    (net (code "50") (name "unconnected-(U$1-Pad14{slash}A0)") (class "Default")
      (node (ref "U$1") (pin "14/A0") (pinfunction "14/A0_14/A0") (pintype "bidirectional"))
    )
    (net (code "51") (name "unconnected-(U$1-PadPGM)") (class "Default")
      (node (ref "U$1") (pin "PGM") (pinfunction "PGM_PGM") (pintype "bidirectional"))
    )
    (net (code "52") (name "unconnected-(U4-EX_ANT-PadP$11)") (class "Default")
      (node (ref "U4") (pin "P$11") (pinfunction "EX_ANT_P$11") (pintype "bidirectional"))
    )
    (net (code "53") (name "unconnected-(U4-NC-PadP$6)") (class "Default")
      (node (ref "U4") (pin "P$6") (pinfunction "NC_P$6") (pintype "bidirectional"))
    )
    (net (code "54") (name "unconnected-(U4-NC-PadP$7)") (class "Default")
      (node (ref "U4") (pin "P$7") (pinfunction "NC_P$7") (pintype "bidirectional"))
    )
    (net (code "55") (name "unconnected-(U4-NC-PadP$15)") (class "Default")
      (node (ref "U4") (pin "P$15") (pinfunction "NC_P$15") (pintype "bidirectional"))
    )
    (net (code "56") (name "unconnected-(U4-NC-PadP$16)") (class "Default")
      (node (ref "U4") (pin "P$16") (pinfunction "NC_P$16") (pintype "bidirectional"))
    )
    (net (code "57") (name "unconnected-(U4-NC-PadP$17)") (class "Default")
      (node (ref "U4") (pin "P$17") (pinfunction "NC_P$17") (pintype "bidirectional"))
    )
    (net (code "58") (name "unconnected-(U4-NC-PadP$18)") (class "Default")
      (node (ref "U4") (pin "P$18") (pinfunction "NC_P$18") (pintype "bidirectional"))
    )
    (net (code "59") (name "unconnected-(U4-NC-PadP$20)") (class "Default")
      (node (ref "U4") (pin "P$20") (pinfunction "NC_P$20") (pintype "bidirectional"))
    )
    (net (code "60") (name "unconnected-(U4-NRESET-PadP$2)") (class "Default")
      (node (ref "U4") (pin "P$2") (pinfunction "NRESET_P$2") (pintype "bidirectional"))
    )
    (net (code "61") (name "unconnected-(U4-RTCM-PadP$14)") (class "Default")
      (node (ref "U4") (pin "P$14") (pinfunction "RTCM_P$14") (pintype "bidirectional"))
    )
  )
)
